# HiddenWiringDetector.net
KiCad netlist of a schematic drawn in Altium Designer
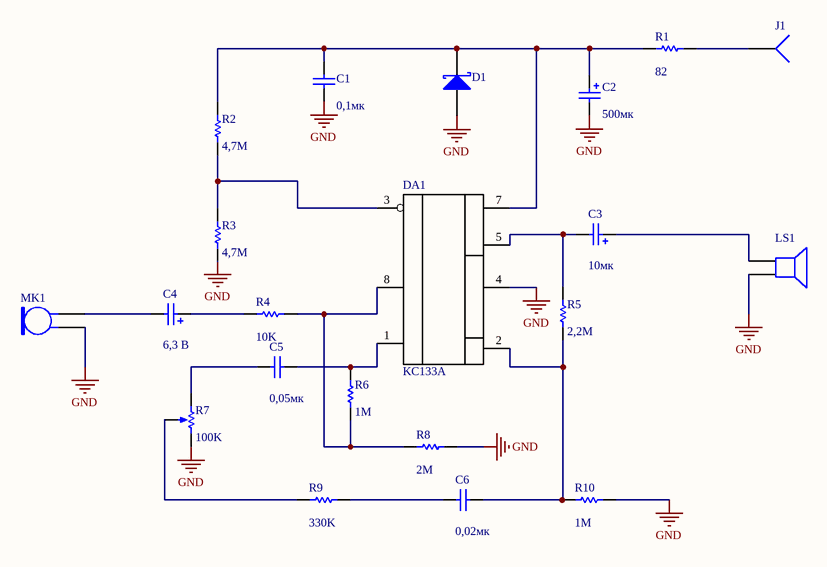
[diagram p0: HiddenWiringDetector.SchDoc]

(export (version "E")
  (design (tool "Eeschema 10.0.6"))
  (components
    (comp (ref "C1")
      (value "0,1мк")
      (footprint "0402")
      (description "Capacitor (Semiconductor SIM Model)")
      (fields (field (name "Comment") "Cap Semi") (field (name "PUBLISHER") "Altium Limited"))
      (libsource (lib "Miscellaneous Devices") (part "Cap Semi"))
    )
    (comp (ref "C2")
      (value "500мк")
      (footprint "POLAR0.8")
      (description "Polarized Capacitor (Axial)")
      (fields (field (name "Comment") "Cap Pol2") (field (name "PUBLISHER") "Altium Limited"))
      (libsource (lib "Miscellaneous Devices") (part "Cap Pol2"))
    )
    (comp (ref "C3")
      (value "10мк")
      (footprint "POLAR0.8")
      (description "Polarized Capacitor (Axial)")
      (fields (field (name "Comment") "Cap Pol2") (field (name "PUBLISHER") "Altium Limited"))
      (libsource (lib "Miscellaneous Devices") (part "Cap Pol2"))
    )
    (comp (ref "C4")
      (value "6,3 B")
      (footprint "POLAR0.8")
      (description "Polarized Capacitor (Axial)")
      (fields (field (name "Comment") "Cap Pol2") (field (name "PUBLISHER") "Altium Limited"))
      (libsource (lib "Miscellaneous Devices") (part "Cap Pol2"))
    )
    (comp (ref "C5")
      (value "0,05мк")
      (footprint "0402")
      (description "Capacitor (Semiconductor SIM Model)")
      (fields (field (name "Comment") "Cap Semi") (field (name "PUBLISHER") "Altium Limited"))
      (libsource (lib "Miscellaneous Devices") (part "Cap Semi"))
    )
    (comp (ref "C6")
      (value "0,02мк")
      (footprint "0402")
      (description "Capacitor (Semiconductor SIM Model)")
      (fields (field (name "Comment") "Cap Semi") (field (name "PUBLISHER") "Altium Limited"))
      (libsource (lib "Miscellaneous Devices") (part "Cap Semi"))
    )
    (comp (ref "D1")
      (value "Diode 11DQ03")
      (footprint "DO-204AL")
      (description "Schottky Rectifier")
      (fields (field (name "PUBLISHER") "Altium Limited"))
      (libsource (lib "Miscellaneous Devices") (part "Diode 11DQ03"))
    )
    (comp (ref "DA1")
      (value "KC133A")
      (footprint "PCBComponent_1")
      (libsource (lib "KC133A") (part "KC133A"))
    )
    (comp (ref "J1")
      (value "Socket")
      (footprint "PIN1")
      (fields (field (name "PUBLISHER") "Altium Limited"))
      (libsource (lib "Miscellaneous Connectors") (part "Socket"))
    )
    (comp (ref "LS1")
      (value "Speaker")
      (footprint "PIN2")
      (description "Loudspeaker")
      (fields (field (name "PUBLISHER") "Altium Limited"))
      (libsource (lib "Miscellaneous Devices") (part "Speaker"))
    )
    (comp (ref "MK1")
      (value "Mic2")
      (footprint "PIN2")
      (description "Microphone")
      (fields (field (name "PUBLISHER") "Altium Limited"))
      (libsource (lib "Miscellaneous Devices") (part "Mic2"))
    )
    (comp (ref "R1")
      (value "82")
      (footprint "AXIAL-0.3")
      (description "Resistor")
      (fields (field (name "Comment") "Res1") (field (name "PUBLISHER") "Altium Limited"))
      (libsource (lib "Miscellaneous Devices") (part "Res1"))
    )
    (comp (ref "R2")
      (value "4,7М")
      (footprint "AXIAL-0.3")
      (description "Resistor")
      (fields (field (name "Comment") "Res1") (field (name "PUBLISHER") "Altium Limited"))
      (libsource (lib "Miscellaneous Devices") (part "Res1"))
    )
    (comp (ref "R3")
      (value "4,7М")
      (footprint "AXIAL-0.3")
      (description "Resistor")
      (fields (field (name "Comment") "Res1") (field (name "PUBLISHER") "Altium Limited"))
      (libsource (lib "Miscellaneous Devices") (part "Res1"))
    )
    (comp (ref "R4")
      (value "10K")
      (footprint "AXIAL-0.3")
      (description "Resistor")
      (fields (field (name "Comment") "Res1") (field (name "PUBLISHER") "Altium Limited"))
      (libsource (lib "Miscellaneous Devices") (part "Res1"))
    )
    (comp (ref "R5")
      (value "2,2М")
      (footprint "AXIAL-0.3")
      (description "Resistor")
      (fields (field (name "PUBLISHER") "Altium Limited"))
      (libsource (lib "Miscellaneous Devices") (part "Res1"))
    )
    (comp (ref "R6")
      (value "1М")
      (footprint "AXIAL-0.3")
      (description "Resistor")
      (fields (field (name "Comment") "Res1") (field (name "PUBLISHER") "Altium Limited"))
      (libsource (lib "Miscellaneous Devices") (part "Res1"))
    )
    (comp (ref "R7")
      (value "100K")
      (footprint "VR5")
      (description "Potentiometer")
      (fields (field (name "Comment") "RPot") (field (name "PUBLISHER") "Altium Limited"))
      (libsource (lib "Miscellaneous Devices") (part "RPot"))
    )
    (comp (ref "R8")
      (value "2М")
      (footprint "AXIAL-0.3")
      (description "Resistor")
      (fields (field (name "Comment") "Res1") (field (name "PUBLISHER") "Altium Limited"))
      (libsource (lib "Miscellaneous Devices") (part "Res1"))
    )
    (comp (ref "R9")
      (value "330K")
      (footprint "AXIAL-0.3")
      (description "Resistor")
      (fields (field (name "Comment") "Res1") (field (name "PUBLISHER") "Altium Limited"))
      (libsource (lib "Miscellaneous Devices") (part "Res1"))
    )
    (comp (ref "R10")
      (value "1М")
      (footprint "AXIAL-0.3")
      (description "Resistor")
      (fields (field (name "Comment") "Res1") (field (name "PUBLISHER") "Altium Limited"))
      (libsource (lib "Miscellaneous Devices") (part "Res1"))
    )
  )
  (nets
    (net (code "1") (name "GND") (class "Default")
      (node (ref "C1") (pin "1") (pinfunction "1_1") (pintype "passive"))
      (node (ref "C2") (pin "2") (pinfunction "2_2") (pintype "passive"))
      (node (ref "D1") (pin "1") (pinfunction "A_1") (pintype "passive"))
      (node (ref "DA1") (pin "4") (pinfunction "4_4") (pintype "passive"))
      (node (ref "LS1") (pin "2") (pinfunction "2_2") (pintype "passive"))
      (node (ref "MK1") (pin "1") (pinfunction "1_1") (pintype "passive"))
      (node (ref "R10") (pin "2") (pinfunction "2_2") (pintype "passive"))
      (node (ref "R3") (pin "1") (pinfunction "1_1") (pintype "passive"))
      (node (ref "R7") (pin "2") (pinfunction "BOT_2") (pintype "passive"))
      (node (ref "R8") (pin "1") (pinfunction "1_1") (pintype "passive"))
    )
    (net (code "2") (name "Net-(C3-Pad1)") (class "Default")
      (node (ref "C3") (pin "1") (pinfunction "1_1") (pintype "passive"))
      (node (ref "LS1") (pin "1") (pinfunction "1_1") (pintype "passive"))
    )
    (net (code "3") (name "Net-(C3-Pad2)") (class "Default")
      (node (ref "C3") (pin "2") (pinfunction "2_2") (pintype "passive"))
      (node (ref "DA1") (pin "5") (pinfunction "5_5") (pintype "passive"))
      (node (ref "R5") (pin "1") (pinfunction "1_1") (pintype "passive"))
    )
    (net (code "4") (name "Net-(C4-Pad1)") (class "Default")
      (node (ref "C4") (pin "1") (pinfunction "1_1") (pintype "passive"))
      (node (ref "R4") (pin "1") (pinfunction "1_1") (pintype "passive"))
    )
    (net (code "5") (name "Net-(C4-Pad2)") (class "Default")
      (node (ref "C4") (pin "2") (pinfunction "2_2") (pintype "passive"))
      (node (ref "MK1") (pin "2") (pinfunction "2_2") (pintype "passive"))
    )
    (net (code "6") (name "Net-(C5-Pad1)") (class "Default")
      (node (ref "C5") (pin "1") (pinfunction "1_1") (pintype "passive"))
      (node (ref "DA1") (pin "1") (pinfunction "1_1") (pintype "passive"))
      (node (ref "R6") (pin "2") (pinfunction "2_2") (pintype "passive"))
    )
    (net (code "7") (name "Net-(C6-Pad1)") (class "Default")
      (node (ref "C6") (pin "1") (pinfunction "1_1") (pintype "passive"))
      (node (ref "DA1") (pin "2") (pinfunction "2_2") (pintype "passive"))
      (node (ref "R10") (pin "1") (pinfunction "1_1") (pintype "passive"))
      (node (ref "R5") (pin "2") (pinfunction "2_2") (pintype "passive"))
    )
    (net (code "8") (name "Net-(C6-Pad2)") (class "Default")
      (node (ref "C6") (pin "2") (pinfunction "2_2") (pintype "passive"))
      (node (ref "R9") (pin "2") (pinfunction "2_2") (pintype "passive"))
    )
    (net (code "9") (name "Net-(D1-K)") (class "Default")
      (node (ref "C1") (pin "2") (pinfunction "2_2") (pintype "passive"))
      (node (ref "C2") (pin "1") (pinfunction "1_1") (pintype "passive"))
      (node (ref "D1") (pin "2") (pinfunction "K_2") (pintype "passive"))
      (node (ref "DA1") (pin "7") (pinfunction "7_7") (pintype "passive"))
      (node (ref "R1") (pin "2") (pinfunction "2_2") (pintype "passive"))
      (node (ref "R2") (pin "2") (pinfunction "2_2") (pintype "passive"))
    )
    (net (code "10") (name "Net-(DA1-Pad3)") (class "Default")
      (node (ref "DA1") (pin "3") (pinfunction "3_3") (pintype "passive"))
      (node (ref "R2") (pin "1") (pinfunction "1_1") (pintype "passive"))
      (node (ref "R3") (pin "2") (pinfunction "2_2") (pintype "passive"))
    )
    (net (code "11") (name "Net-(DA1-Pad8)") (class "Default")
      (node (ref "DA1") (pin "8") (pinfunction "8_8") (pintype "passive"))
      (node (ref "R4") (pin "2") (pinfunction "2_2") (pintype "passive"))
      (node (ref "R6") (pin "1") (pinfunction "1_1") (pintype "passive"))
      (node (ref "R8") (pin "2") (pinfunction "2_2") (pintype "passive"))
    )
    (net (code "12") (name "Net-(J1-Pad1)") (class "Default")
      (node (ref "J1") (pin "1") (pinfunction "1_1") (pintype "passive"))
      (node (ref "R1") (pin "1") (pinfunction "1_1") (pintype "passive"))
    )
    (net (code "13") (name "Net-(R7-TAP)") (class "Default")
      (node (ref "R7") (pin "3") (pinfunction "TAP_3") (pintype "passive"))
      (node (ref "R9") (pin "1") (pinfunction "1_1") (pintype "passive"))
    )
    (net (code "14") (name "Net-(R7-TOP)") (class "Default")
      (node (ref "C5") (pin "2") (pinfunction "2_2") (pintype "passive"))
      (node (ref "R7") (pin "1") (pinfunction "TOP_1") (pintype "passive"))
    )
  )
)
